# ardulight.net
KiCad netlist of a schematic drawn in EAGLE
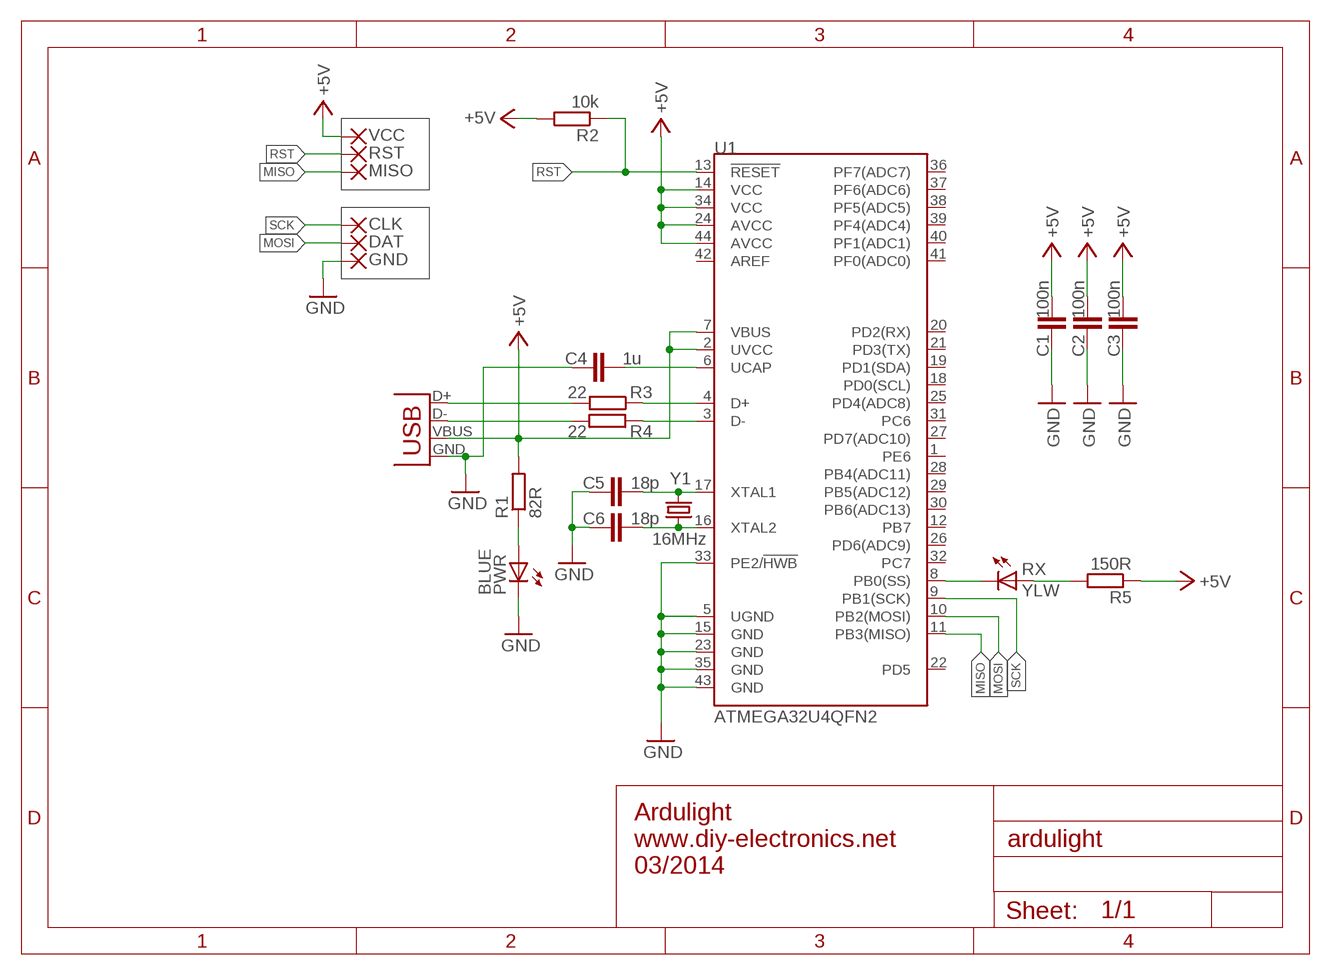
[diagram p0: schematic, sheet 1]

(export (version "E")
  (design (tool "Eeschema 10.0.6"))
  (components
    (comp (ref "C1")
      (value "100n")
      (footprint "eagle-import:C0603")
      (libsource (lib "eagle-import") (part "C-EUC0603"))
    )
    (comp (ref "C2")
      (value "100n")
      (footprint "eagle-import:C0603")
      (libsource (lib "eagle-import") (part "C-EUC0603"))
    )
    (comp (ref "C3")
      (value "100n")
      (footprint "eagle-import:C0603")
      (libsource (lib "eagle-import") (part "C-EUC0603"))
    )
    (comp (ref "C4")
      (value "1u")
      (footprint "eagle-import:C0603")
      (libsource (lib "eagle-import") (part "C-EUC0603"))
    )
    (comp (ref "C5")
      (value "18p")
      (footprint "eagle-import:C0603")
      (libsource (lib "eagle-import") (part "C-EUC0603"))
    )
    (comp (ref "C6")
      (value "18p")
      (footprint "eagle-import:C0603")
      (libsource (lib "eagle-import") (part "C-EUC0603"))
    )
    (comp (ref "CLK")
      (value "SMD5")
      (footprint "eagle-import:SMD2,54-5,08")
      (libsource (lib "eagle-import") (part "SMD5"))
    )
    (comp (ref "DAT")
      (value "SMD5")
      (footprint "eagle-import:SMD2,54-5,08")
      (libsource (lib "eagle-import") (part "SMD5"))
    )
    (comp (ref "GND")
      (value "SMD5")
      (footprint "eagle-import:SMD2,54-5,08")
      (libsource (lib "eagle-import") (part "SMD5"))
    )
    (comp (ref "JP1")
      (value "USBSMD")
      (footprint "eagle-import:USB-MINIB")
      (libsource (lib "eagle-import") (part "USBSMD"))
    )
    (comp (ref "MISO")
      (value "SMD2")
      (footprint "eagle-import:SMD1,27-2,54")
      (libsource (lib "eagle-import") (part "SMD2"))
    )
    (comp (ref "PWR")
      (value "BLUE")
      (footprint "eagle-import:CHIPLED_0603")
      (libsource (lib "eagle-import") (part "LEDCHIPLED_0603"))
    )
    (comp (ref "R1")
      (value "82R")
      (footprint "eagle-import:R0603")
      (libsource (lib "eagle-import") (part "R-EU_R0603"))
    )
    (comp (ref "R2")
      (value "10k")
      (footprint "eagle-import:R0603")
      (libsource (lib "eagle-import") (part "R-EU_R0603"))
    )
    (comp (ref "R3")
      (value "22")
      (footprint "eagle-import:R0603")
      (libsource (lib "eagle-import") (part "R-EU_R0603"))
    )
    (comp (ref "R4")
      (value "22")
      (footprint "eagle-import:R0603")
      (libsource (lib "eagle-import") (part "R-EU_R0603"))
    )
    (comp (ref "R5")
      (value "150R")
      (footprint "eagle-import:R0603")
      (libsource (lib "eagle-import") (part "R-EU_R0603"))
    )
    (comp (ref "RST")
      (value "SMD2")
      (footprint "eagle-import:SMD1,27-2,54")
      (libsource (lib "eagle-import") (part "SMD2"))
    )
    (comp (ref "RX")
      (value "YLW")
      (footprint "eagle-import:CHIPLED_0603")
      (libsource (lib "eagle-import") (part "LEDCHIPLED_0603"))
    )
    (comp (ref "U1")
      (value "ATMEGA32U4QFN2")
      (footprint "eagle-import:SPARKFUN-DIGITALIC_QFN-44-NOPAD")
      (libsource (lib "eagle-import") (part "ATMEGA32U4QFN2"))
    )
    (comp (ref "VCC")
      (value "SMD2")
      (footprint "eagle-import:SMD1,27-2,54")
      (libsource (lib "eagle-import") (part "SMD2"))
    )
    (comp (ref "Y1")
      (value "16MHz")
      (footprint "eagle-import:CRYSTAL-SMD-5X3")
      (libsource (lib "eagle-import") (part "CRYSTAL5X3"))
    )
  )
  (nets
    (net (code "1") (name "+5V") (class "Default")
      (node (ref "C1") (pin "2") (pinfunction "2_2") (pintype "passive"))
      (node (ref "C2") (pin "2") (pinfunction "2_2") (pintype "passive"))
      (node (ref "C3") (pin "2") (pinfunction "2_2") (pintype "passive"))
      (node (ref "JP1") (pin "VBUS") (pinfunction "VBUS_VBUS") (pintype "bidirectional"))
      (node (ref "R1") (pin "2") (pinfunction "2_2") (pintype "passive"))
      (node (ref "R2") (pin "2") (pinfunction "2_2") (pintype "passive"))
      (node (ref "R5") (pin "1") (pinfunction "1_1") (pintype "passive"))
      (node (ref "U1") (pin "14") (pinfunction "VCC_14") (pintype "bidirectional"))
      (node (ref "U1") (pin "2") (pinfunction "UVCC_2") (pintype "bidirectional"))
      (node (ref "U1") (pin "24") (pinfunction "AVCC_24") (pintype "bidirectional"))
      (node (ref "U1") (pin "34") (pinfunction "VCC_34") (pintype "bidirectional"))
      (node (ref "U1") (pin "44") (pinfunction "AVCC_44") (pintype "bidirectional"))
      (node (ref "U1") (pin "7") (pinfunction "VBUS_7") (pintype "bidirectional"))
      (node (ref "VCC") (pin "1") (pinfunction "P_1") (pintype "passive"))
    )
    (net (code "2") (name "GND") (class "Default")
      (node (ref "C1") (pin "1") (pinfunction "1_1") (pintype "passive"))
      (node (ref "C2") (pin "1") (pinfunction "1_1") (pintype "passive"))
      (node (ref "C3") (pin "1") (pinfunction "1_1") (pintype "passive"))
      (node (ref "C4") (pin "1") (pinfunction "1_1") (pintype "passive"))
      (node (ref "C5") (pin "1") (pinfunction "1_1") (pintype "passive"))
      (node (ref "C6") (pin "1") (pinfunction "1_1") (pintype "passive"))
      (node (ref "GND") (pin "1") (pinfunction "P_1") (pintype "passive"))
      (node (ref "JP1") (pin "GND") (pinfunction "GND_GND") (pintype "bidirectional"))
      (node (ref "PWR") (pin "C") (pinfunction "C_C") (pintype "passive"))
      (node (ref "U1") (pin "15") (pinfunction "GND_15") (pintype "bidirectional"))
      (node (ref "U1") (pin "23") (pinfunction "GND_23") (pintype "bidirectional"))
      (node (ref "U1") (pin "33") (pinfunction "PE2/~{HWB}_33") (pintype "bidirectional"))
      (node (ref "U1") (pin "35") (pinfunction "GND_35") (pintype "bidirectional"))
      (node (ref "U1") (pin "43") (pinfunction "GND_43") (pintype "bidirectional"))
      (node (ref "U1") (pin "5") (pinfunction "UGND_5") (pintype "bidirectional"))
    )
    (net (code "3") (name "MISO") (class "Default")
      (node (ref "MISO") (pin "1") (pinfunction "P_1") (pintype "passive"))
      (node (ref "U1") (pin "11") (pinfunction "PB3(MISO)_11") (pintype "bidirectional"))
    )
    (net (code "4") (name "MOSI") (class "Default")
      (node (ref "DAT") (pin "1") (pinfunction "P_1") (pintype "passive"))
      (node (ref "U1") (pin "10") (pinfunction "PB2(MOSI)_10") (pintype "bidirectional"))
    )
    (net (code "5") (name "Net-(JP1-PadD+)") (class "Default")
      (node (ref "JP1") (pin "D+") (pinfunction "D+_D+") (pintype "bidirectional"))
      (node (ref "R3") (pin "2") (pinfunction "2_2") (pintype "passive"))
    )
    (net (code "6") (name "Net-(JP1-PadD-)") (class "Default")
      (node (ref "JP1") (pin "D-") (pinfunction "D-_D-") (pintype "bidirectional"))
      (node (ref "R4") (pin "2") (pinfunction "2_2") (pintype "passive"))
    )
    (net (code "7") (name "Net-(PWR-PadA)") (class "Default")
      (node (ref "PWR") (pin "A") (pinfunction "A_A") (pintype "passive"))
      (node (ref "R1") (pin "1") (pinfunction "1_1") (pintype "passive"))
    )
    (net (code "8") (name "Net-(R5-Pad2)") (class "Default")
      (node (ref "R5") (pin "2") (pinfunction "2_2") (pintype "passive"))
      (node (ref "RX") (pin "A") (pinfunction "A_A") (pintype "passive"))
    )
    (net (code "9") (name "Net-(U1-D+)") (class "Default")
      (node (ref "R3") (pin "1") (pinfunction "1_1") (pintype "passive"))
      (node (ref "U1") (pin "4") (pinfunction "D+_4") (pintype "bidirectional"))
    )
    (net (code "10") (name "Net-(U1-D-)") (class "Default")
      (node (ref "R4") (pin "1") (pinfunction "1_1") (pintype "passive"))
      (node (ref "U1") (pin "3") (pinfunction "D-_3") (pintype "bidirectional"))
    )
    (net (code "11") (name "Net-(U1-PB0(SS))") (class "Default")
      (node (ref "RX") (pin "C") (pinfunction "C_C") (pintype "passive"))
      (node (ref "U1") (pin "8") (pinfunction "PB0(SS)_8") (pintype "bidirectional"))
    )
    (net (code "12") (name "Net-(U1-UCAP)") (class "Default")
      (node (ref "C4") (pin "2") (pinfunction "2_2") (pintype "passive"))
      (node (ref "U1") (pin "6") (pinfunction "UCAP_6") (pintype "bidirectional"))
    )
    (net (code "13") (name "Net-(U1-XTAL1)") (class "Default")
      (node (ref "C5") (pin "2") (pinfunction "2_2") (pintype "passive"))
      (node (ref "U1") (pin "17") (pinfunction "XTAL1_17") (pintype "bidirectional"))
      (node (ref "Y1") (pin "3") (pinfunction "2_3") (pintype "passive"))
    )
    (net (code "14") (name "Net-(U1-XTAL2)") (class "Default")
      (node (ref "C6") (pin "2") (pinfunction "2_2") (pintype "passive"))
      (node (ref "U1") (pin "16") (pinfunction "XTAL2_16") (pintype "bidirectional"))
      (node (ref "Y1") (pin "1") (pinfunction "1_1") (pintype "passive"))
    )
    (net (code "15") (name "RST") (class "Default")
      (node (ref "R2") (pin "1") (pinfunction "1_1") (pintype "passive"))
      (node (ref "RST") (pin "1") (pinfunction "P_1") (pintype "passive"))
      (node (ref "U1") (pin "13") (pinfunction "~{RESET}_13") (pintype "bidirectional"))
    )
    (net (code "16") (name "SCK") (class "Default")
      (node (ref "CLK") (pin "1") (pinfunction "P_1") (pintype "passive"))
      (node (ref "U1") (pin "9") (pinfunction "PB1(SCK)_9") (pintype "bidirectional"))
    )
    (net (code "17") (name "unconnected-(U1-AREF-Pad42)") (class "Default")
      (node (ref "U1") (pin "42") (pinfunction "AREF_42") (pintype "bidirectional"))
    )
    (net (code "18") (name "unconnected-(U1-PB4(ADC11)-Pad28)") (class "Default")
      (node (ref "U1") (pin "28") (pinfunction "PB4(ADC11)_28") (pintype "bidirectional"))
    )
    (net (code "19") (name "unconnected-(U1-PB5(ADC12)-Pad29)") (class "Default")
      (node (ref "U1") (pin "29") (pinfunction "PB5(ADC12)_29") (pintype "bidirectional"))
    )
    (net (code "20") (name "unconnected-(U1-PB6(ADC13)-Pad30)") (class "Default")
      (node (ref "U1") (pin "30") (pinfunction "PB6(ADC13)_30") (pintype "bidirectional"))
    )
    (net (code "21") (name "unconnected-(U1-PB7-Pad12)") (class "Default")
      (node (ref "U1") (pin "12") (pinfunction "PB7_12") (pintype "bidirectional"))
    )
    (net (code "22") (name "unconnected-(U1-PC6-Pad31)") (class "Default")
      (node (ref "U1") (pin "31") (pinfunction "PC6_31") (pintype "bidirectional"))
    )
    (net (code "23") (name "unconnected-(U1-PC7-Pad32)") (class "Default")
      (node (ref "U1") (pin "32") (pinfunction "PC7_32") (pintype "bidirectional"))
    )
    (net (code "24") (name "unconnected-(U1-PD0(SCL)-Pad18)") (class "Default")
      (node (ref "U1") (pin "18") (pinfunction "PD0(SCL)_18") (pintype "bidirectional"))
    )
    (net (code "25") (name "unconnected-(U1-PD1(SDA)-Pad19)") (class "Default")
      (node (ref "U1") (pin "19") (pinfunction "PD1(SDA)_19") (pintype "bidirectional"))
    )
    (net (code "26") (name "unconnected-(U1-PD2(RX)-Pad20)") (class "Default")
      (node (ref "U1") (pin "20") (pinfunction "PD2(RX)_20") (pintype "bidirectional"))
    )
    (net (code "27") (name "unconnected-(U1-PD3(TX)-Pad21)") (class "Default")
      (node (ref "U1") (pin "21") (pinfunction "PD3(TX)_21") (pintype "bidirectional"))
    )
    (net (code "28") (name "unconnected-(U1-PD4(ADC8)-Pad25)") (class "Default")
      (node (ref "U1") (pin "25") (pinfunction "PD4(ADC8)_25") (pintype "bidirectional"))
    )
    (net (code "29") (name "unconnected-(U1-PD5-Pad22)") (class "Default")
      (node (ref "U1") (pin "22") (pinfunction "PD5_22") (pintype "bidirectional"))
    )
    (net (code "30") (name "unconnected-(U1-PD6(ADC9)-Pad26)") (class "Default")
      (node (ref "U1") (pin "26") (pinfunction "PD6(ADC9)_26") (pintype "bidirectional"))
    )
    (net (code "31") (name "unconnected-(U1-PD7(ADC10)-Pad27)") (class "Default")
      (node (ref "U1") (pin "27") (pinfunction "PD7(ADC10)_27") (pintype "bidirectional"))
    )
    (net (code "32") (name "unconnected-(U1-PE6-Pad1)") (class "Default")
      (node (ref "U1") (pin "1") (pinfunction "PE6_1") (pintype "bidirectional"))
    )
    (net (code "33") (name "unconnected-(U1-PF0(ADC0)-Pad41)") (class "Default")
      (node (ref "U1") (pin "41") (pinfunction "PF0(ADC0)_41") (pintype "bidirectional"))
    )
    (net (code "34") (name "unconnected-(U1-PF1(ADC1)-Pad40)") (class "Default")
      (node (ref "U1") (pin "40") (pinfunction "PF1(ADC1)_40") (pintype "bidirectional"))
    )
    (net (code "35") (name "unconnected-(U1-PF4(ADC4)-Pad39)") (class "Default")
      (node (ref "U1") (pin "39") (pinfunction "PF4(ADC4)_39") (pintype "bidirectional"))
    )
    (net (code "36") (name "unconnected-(U1-PF5(ADC5)-Pad38)") (class "Default")
      (node (ref "U1") (pin "38") (pinfunction "PF5(ADC5)_38") (pintype "bidirectional"))
    )
    (net (code "37") (name "unconnected-(U1-PF6(ADC6)-Pad37)") (class "Default")
      (node (ref "U1") (pin "37") (pinfunction "PF6(ADC6)_37") (pintype "bidirectional"))
    )
    (net (code "38") (name "unconnected-(U1-PF7(ADC7)-Pad36)") (class "Default")
      (node (ref "U1") (pin "36") (pinfunction "PF7(ADC7)_36") (pintype "bidirectional"))
    )
  )
)
